# Daisy_Test.net
KiCad netlist of a schematic drawn in EAGLE
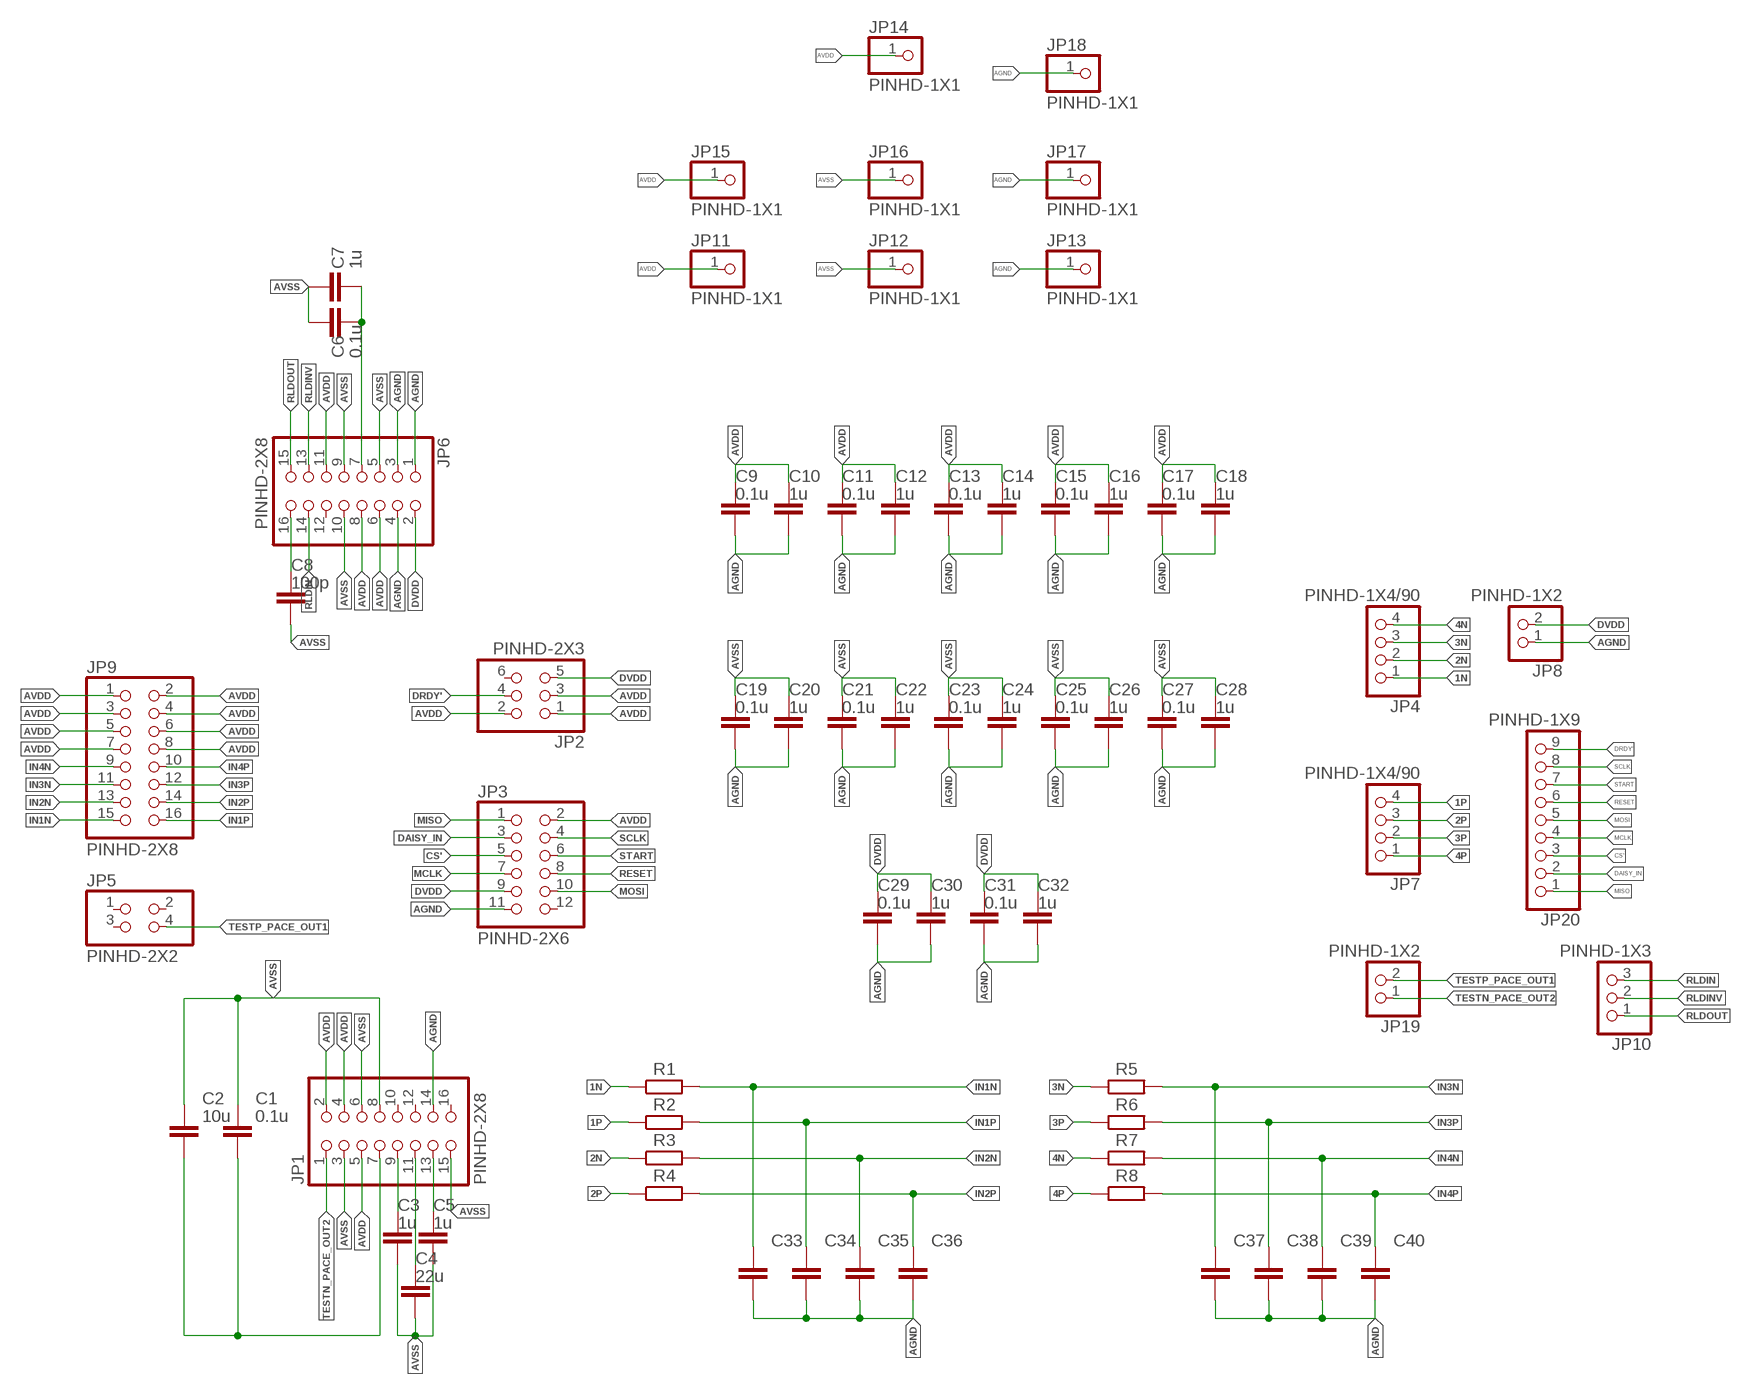
[diagram p0: schematic, sheet 1]

(export (version "E")
  (design (tool "Eeschema 10.0.6"))
  (components
    (comp (ref "C1")
      (value "0.1u")
      (footprint "eagle-import:CAPC2012X110")
      (libsource (lib "eagle-import") (part "CCHIP-0805(2012-METRIC)_"))
    )
    (comp (ref "C2")
      (value "10u")
      (footprint "eagle-import:CAPC2012X110")
      (libsource (lib "eagle-import") (part "CCHIP-0805(2012-METRIC)_"))
    )
    (comp (ref "C3")
      (value "1u")
      (footprint "eagle-import:CAPC2012X110")
      (libsource (lib "eagle-import") (part "CCHIP-0805(2012-METRIC)_"))
    )
    (comp (ref "C4")
      (value "22u")
      (footprint "eagle-import:CAPC2012X110")
      (libsource (lib "eagle-import") (part "CCHIP-0805(2012-METRIC)_"))
    )
    (comp (ref "C5")
      (value "1u")
      (footprint "eagle-import:CAPC2012X110")
      (libsource (lib "eagle-import") (part "CCHIP-0805(2012-METRIC)_"))
    )
    (comp (ref "C6")
      (value "0.1u")
      (footprint "eagle-import:CAPC2012X110")
      (libsource (lib "eagle-import") (part "CCHIP-0805(2012-METRIC)_"))
    )
    (comp (ref "C7")
      (value "1u")
      (footprint "eagle-import:CAPC2012X110")
      (libsource (lib "eagle-import") (part "CCHIP-0805(2012-METRIC)_"))
    )
    (comp (ref "C8")
      (value "100p")
      (footprint "eagle-import:CAPC2012X110")
      (libsource (lib "eagle-import") (part "CCHIP-0805(2012-METRIC)_"))
    )
    (comp (ref "C9")
      (value "0.1u")
      (footprint "eagle-import:CAPC2012X110")
      (libsource (lib "eagle-import") (part "CCHIP-0805(2012-METRIC)_"))
    )
    (comp (ref "C10")
      (value "1u")
      (footprint "eagle-import:CAPC2012X110")
      (libsource (lib "eagle-import") (part "CCHIP-0805(2012-METRIC)_"))
    )
    (comp (ref "C11")
      (value "0.1u")
      (footprint "eagle-import:CAPC2012X110")
      (libsource (lib "eagle-import") (part "CCHIP-0805(2012-METRIC)_"))
    )
    (comp (ref "C12")
      (value "1u")
      (footprint "eagle-import:CAPC2012X110")
      (libsource (lib "eagle-import") (part "CCHIP-0805(2012-METRIC)_"))
    )
    (comp (ref "C13")
      (value "0.1u")
      (footprint "eagle-import:CAPC2012X110")
      (libsource (lib "eagle-import") (part "CCHIP-0805(2012-METRIC)_"))
    )
    (comp (ref "C14")
      (value "1u")
      (footprint "eagle-import:CAPC2012X110")
      (libsource (lib "eagle-import") (part "CCHIP-0805(2012-METRIC)_"))
    )
    (comp (ref "C15")
      (value "0.1u")
      (footprint "eagle-import:CAPC2012X110")
      (libsource (lib "eagle-import") (part "CCHIP-0805(2012-METRIC)_"))
    )
    (comp (ref "C16")
      (value "1u")
      (footprint "eagle-import:CAPC2012X110")
      (libsource (lib "eagle-import") (part "CCHIP-0805(2012-METRIC)_"))
    )
    (comp (ref "C17")
      (value "0.1u")
      (footprint "eagle-import:CAPC2012X110")
      (libsource (lib "eagle-import") (part "CCHIP-0805(2012-METRIC)_"))
    )
    (comp (ref "C18")
      (value "1u")
      (footprint "eagle-import:CAPC2012X110")
      (libsource (lib "eagle-import") (part "CCHIP-0805(2012-METRIC)_"))
    )
    (comp (ref "C19")
      (value "0.1u")
      (footprint "eagle-import:CAPC2012X110")
      (libsource (lib "eagle-import") (part "CCHIP-0805(2012-METRIC)_"))
    )
    (comp (ref "C20")
      (value "1u")
      (footprint "eagle-import:CAPC2012X110")
      (libsource (lib "eagle-import") (part "CCHIP-0805(2012-METRIC)_"))
    )
    (comp (ref "C21")
      (value "0.1u")
      (footprint "eagle-import:CAPC2012X110")
      (libsource (lib "eagle-import") (part "CCHIP-0805(2012-METRIC)_"))
    )
    (comp (ref "C22")
      (value "1u")
      (footprint "eagle-import:CAPC2012X110")
      (libsource (lib "eagle-import") (part "CCHIP-0805(2012-METRIC)_"))
    )
    (comp (ref "C23")
      (value "0.1u")
      (footprint "eagle-import:CAPC2012X110")
      (libsource (lib "eagle-import") (part "CCHIP-0805(2012-METRIC)_"))
    )
    (comp (ref "C24")
      (value "1u")
      (footprint "eagle-import:CAPC2012X110")
      (libsource (lib "eagle-import") (part "CCHIP-0805(2012-METRIC)_"))
    )
    (comp (ref "C25")
      (value "0.1u")
      (footprint "eagle-import:CAPC2012X110")
      (libsource (lib "eagle-import") (part "CCHIP-0805(2012-METRIC)_"))
    )
    (comp (ref "C26")
      (value "1u")
      (footprint "eagle-import:CAPC2012X110")
      (libsource (lib "eagle-import") (part "CCHIP-0805(2012-METRIC)_"))
    )
    (comp (ref "C27")
      (value "0.1u")
      (footprint "eagle-import:CAPC2012X110")
      (libsource (lib "eagle-import") (part "CCHIP-0805(2012-METRIC)_"))
    )
    (comp (ref "C28")
      (value "1u")
      (footprint "eagle-import:CAPC2012X110")
      (libsource (lib "eagle-import") (part "CCHIP-0805(2012-METRIC)_"))
    )
    (comp (ref "C29")
      (value "0.1u")
      (footprint "eagle-import:CAPC2012X110")
      (libsource (lib "eagle-import") (part "CCHIP-0805(2012-METRIC)_"))
    )
    (comp (ref "C30")
      (value "1u")
      (footprint "eagle-import:CAPC2012X110")
      (libsource (lib "eagle-import") (part "CCHIP-0805(2012-METRIC)_"))
    )
    (comp (ref "C31")
      (value "0.1u")
      (footprint "eagle-import:CAPC2012X110")
      (libsource (lib "eagle-import") (part "CCHIP-0805(2012-METRIC)_"))
    )
    (comp (ref "C32")
      (value "1u")
      (footprint "eagle-import:CAPC2012X110")
      (libsource (lib "eagle-import") (part "CCHIP-0805(2012-METRIC)_"))
    )
    (comp (ref "C33")
      (value "C_CHIP-0805(2012-METRIC)")
      (footprint "eagle-import:CAPC2012X110")
      (libsource (lib "eagle-import") (part "CCHIP-0805(2012-METRIC)_"))
    )
    (comp (ref "C34")
      (value "C_CHIP-0805(2012-METRIC)")
      (footprint "eagle-import:CAPC2012X110")
      (libsource (lib "eagle-import") (part "CCHIP-0805(2012-METRIC)_"))
    )
    (comp (ref "C35")
      (value "C_CHIP-0805(2012-METRIC)")
      (footprint "eagle-import:CAPC2012X110")
      (libsource (lib "eagle-import") (part "CCHIP-0805(2012-METRIC)_"))
    )
    (comp (ref "C36")
      (value "C_CHIP-0805(2012-METRIC)")
      (footprint "eagle-import:CAPC2012X110")
      (libsource (lib "eagle-import") (part "CCHIP-0805(2012-METRIC)_"))
    )
    (comp (ref "C37")
      (value "C_CHIP-0805(2012-METRIC)")
      (footprint "eagle-import:CAPC2012X110")
      (libsource (lib "eagle-import") (part "CCHIP-0805(2012-METRIC)_"))
    )
    (comp (ref "C38")
      (value "C_CHIP-0805(2012-METRIC)")
      (footprint "eagle-import:CAPC2012X110")
      (libsource (lib "eagle-import") (part "CCHIP-0805(2012-METRIC)_"))
    )
    (comp (ref "C39")
      (value "C_CHIP-0805(2012-METRIC)")
      (footprint "eagle-import:CAPC2012X110")
      (libsource (lib "eagle-import") (part "CCHIP-0805(2012-METRIC)_"))
    )
    (comp (ref "C40")
      (value "C_CHIP-0805(2012-METRIC)")
      (footprint "eagle-import:CAPC2012X110")
      (libsource (lib "eagle-import") (part "CCHIP-0805(2012-METRIC)_"))
    )
    (comp (ref "JP1")
      (value "PINHD-2X8")
      (footprint "eagle-import:2X08")
      (libsource (lib "eagle-import") (part "PINHD-2X8"))
    )
    (comp (ref "JP2")
      (value "PINHD-2X3")
      (footprint "eagle-import:2X03")
      (libsource (lib "eagle-import") (part "PINHD-2X3"))
    )
    (comp (ref "JP3")
      (value "PINHD-2X6")
      (footprint "eagle-import:2X06")
      (libsource (lib "eagle-import") (part "PINHD-2X6"))
    )
    (comp (ref "JP4")
      (value "PINHD-1X4/90")
      (footprint "eagle-import:1X04_90")
      (libsource (lib "eagle-import") (part "PINHD-1X4/90"))
    )
    (comp (ref "JP5")
      (value "PINHD-2X2")
      (footprint "eagle-import:2X02")
      (libsource (lib "eagle-import") (part "PINHD-2X2"))
    )
    (comp (ref "JP6")
      (value "PINHD-2X8")
      (footprint "eagle-import:2X08")
      (libsource (lib "eagle-import") (part "PINHD-2X8"))
    )
    (comp (ref "JP7")
      (value "PINHD-1X4/90")
      (footprint "eagle-import:1X04_90")
      (libsource (lib "eagle-import") (part "PINHD-1X4/90"))
    )
    (comp (ref "JP8")
      (value "PINHD-1X2")
      (footprint "eagle-import:1X02")
      (libsource (lib "eagle-import") (part "PINHD-1X2"))
    )
    (comp (ref "JP9")
      (value "PINHD-2X8")
      (footprint "eagle-import:2X08")
      (libsource (lib "eagle-import") (part "PINHD-2X8"))
    )
    (comp (ref "JP10")
      (value "PINHD-1X3")
      (footprint "eagle-import:1X03")
      (libsource (lib "eagle-import") (part "PINHD-1X3"))
    )
    (comp (ref "JP11")
      (value "PINHD-1X1")
      (footprint "eagle-import:1X01")
      (libsource (lib "eagle-import") (part "PINHD-1X1"))
    )
    (comp (ref "JP12")
      (value "PINHD-1X1")
      (footprint "eagle-import:1X01")
      (libsource (lib "eagle-import") (part "PINHD-1X1"))
    )
    (comp (ref "JP13")
      (value "PINHD-1X1")
      (footprint "eagle-import:1X01")
      (libsource (lib "eagle-import") (part "PINHD-1X1"))
    )
    (comp (ref "JP14")
      (value "PINHD-1X1")
      (footprint "eagle-import:1X01")
      (libsource (lib "eagle-import") (part "PINHD-1X1"))
    )
    (comp (ref "JP15")
      (value "PINHD-1X1")
      (footprint "eagle-import:1X01")
      (libsource (lib "eagle-import") (part "PINHD-1X1"))
    )
    (comp (ref "JP16")
      (value "PINHD-1X1")
      (footprint "eagle-import:1X01")
      (libsource (lib "eagle-import") (part "PINHD-1X1"))
    )
    (comp (ref "JP17")
      (value "PINHD-1X1")
      (footprint "eagle-import:1X01")
      (libsource (lib "eagle-import") (part "PINHD-1X1"))
    )
    (comp (ref "JP18")
      (value "PINHD-1X1")
      (footprint "eagle-import:1X01")
      (libsource (lib "eagle-import") (part "PINHD-1X1"))
    )
    (comp (ref "JP19")
      (value "PINHD-1X2")
      (footprint "eagle-import:1X02")
      (libsource (lib "eagle-import") (part "PINHD-1X2"))
    )
    (comp (ref "JP20")
      (value "PINHD-1X9")
      (footprint "eagle-import:1X09")
      (libsource (lib "eagle-import") (part "PINHD-1X9"))
    )
    (comp (ref "R1")
      (value "R_CHIP-1206(3216-METRIC)")
      (footprint "eagle-import:RESC3216X70")
      (libsource (lib "eagle-import") (part "RCHIP-1206(3216-METRIC)_"))
    )
    (comp (ref "R2")
      (value "R_CHIP-1206(3216-METRIC)")
      (footprint "eagle-import:RESC3216X70")
      (libsource (lib "eagle-import") (part "RCHIP-1206(3216-METRIC)_"))
    )
    (comp (ref "R3")
      (value "R_CHIP-1206(3216-METRIC)")
      (footprint "eagle-import:RESC3216X70")
      (libsource (lib "eagle-import") (part "RCHIP-1206(3216-METRIC)_"))
    )
    (comp (ref "R4")
      (value "R_CHIP-1206(3216-METRIC)")
      (footprint "eagle-import:RESC3216X70")
      (libsource (lib "eagle-import") (part "RCHIP-1206(3216-METRIC)_"))
    )
    (comp (ref "R5")
      (value "R_CHIP-1206(3216-METRIC)")
      (footprint "eagle-import:RESC3216X70")
      (libsource (lib "eagle-import") (part "RCHIP-1206(3216-METRIC)_"))
    )
    (comp (ref "R6")
      (value "R_CHIP-1206(3216-METRIC)")
      (footprint "eagle-import:RESC3216X70")
      (libsource (lib "eagle-import") (part "RCHIP-1206(3216-METRIC)_"))
    )
    (comp (ref "R7")
      (value "R_CHIP-1206(3216-METRIC)")
      (footprint "eagle-import:RESC3216X70")
      (libsource (lib "eagle-import") (part "RCHIP-1206(3216-METRIC)_"))
    )
    (comp (ref "R8")
      (value "R_CHIP-1206(3216-METRIC)")
      (footprint "eagle-import:RESC3216X70")
      (libsource (lib "eagle-import") (part "RCHIP-1206(3216-METRIC)_"))
    )
  )
  (nets
    (net (code "1") (name "1N") (class "Default")
      (node (ref "JP4") (pin "1") (pinfunction "1_1") (pintype "passive"))
      (node (ref "R1") (pin "1") (pinfunction "1_1") (pintype "passive"))
    )
    (net (code "2") (name "1P") (class "Default")
      (node (ref "JP7") (pin "4") (pinfunction "4_4") (pintype "passive"))
      (node (ref "R2") (pin "1") (pinfunction "1_1") (pintype "passive"))
    )
    (net (code "3") (name "2N") (class "Default")
      (node (ref "JP4") (pin "2") (pinfunction "2_2") (pintype "passive"))
      (node (ref "R3") (pin "1") (pinfunction "1_1") (pintype "passive"))
    )
    (net (code "4") (name "2P") (class "Default")
      (node (ref "JP7") (pin "3") (pinfunction "3_3") (pintype "passive"))
      (node (ref "R4") (pin "1") (pinfunction "1_1") (pintype "passive"))
    )
    (net (code "5") (name "3N") (class "Default")
      (node (ref "JP4") (pin "3") (pinfunction "3_3") (pintype "passive"))
      (node (ref "R5") (pin "1") (pinfunction "1_1") (pintype "passive"))
    )
    (net (code "6") (name "3P") (class "Default")
      (node (ref "JP7") (pin "2") (pinfunction "2_2") (pintype "passive"))
      (node (ref "R6") (pin "1") (pinfunction "1_1") (pintype "passive"))
    )
    (net (code "7") (name "4N") (class "Default")
      (node (ref "JP4") (pin "4") (pinfunction "4_4") (pintype "passive"))
      (node (ref "R7") (pin "1") (pinfunction "1_1") (pintype "passive"))
    )
    (net (code "8") (name "4P") (class "Default")
      (node (ref "JP7") (pin "1") (pinfunction "1_1") (pintype "passive"))
      (node (ref "R8") (pin "1") (pinfunction "1_1") (pintype "passive"))
    )
    (net (code "9") (name "AGND") (class "Default")
      (node (ref "C10") (pin "2") (pinfunction "2_2") (pintype "passive"))
      (node (ref "C11") (pin "2") (pinfunction "2_2") (pintype "passive"))
      (node (ref "C12") (pin "2") (pinfunction "2_2") (pintype "passive"))
      (node (ref "C13") (pin "2") (pinfunction "2_2") (pintype "passive"))
      (node (ref "C14") (pin "2") (pinfunction "2_2") (pintype "passive"))
      (node (ref "C15") (pin "2") (pinfunction "2_2") (pintype "passive"))
      (node (ref "C16") (pin "2") (pinfunction "2_2") (pintype "passive"))
      (node (ref "C17") (pin "2") (pinfunction "2_2") (pintype "passive"))
      (node (ref "C18") (pin "2") (pinfunction "2_2") (pintype "passive"))
      (node (ref "C19") (pin "2") (pinfunction "2_2") (pintype "passive"))
      (node (ref "C20") (pin "2") (pinfunction "2_2") (pintype "passive"))
      (node (ref "C21") (pin "2") (pinfunction "2_2") (pintype "passive"))
      (node (ref "C22") (pin "2") (pinfunction "2_2") (pintype "passive"))
      (node (ref "C23") (pin "2") (pinfunction "2_2") (pintype "passive"))
      (node (ref "C24") (pin "2") (pinfunction "2_2") (pintype "passive"))
      (node (ref "C25") (pin "2") (pinfunction "2_2") (pintype "passive"))
      (node (ref "C26") (pin "2") (pinfunction "2_2") (pintype "passive"))
      (node (ref "C27") (pin "2") (pinfunction "2_2") (pintype "passive"))
      (node (ref "C28") (pin "2") (pinfunction "2_2") (pintype "passive"))
      (node (ref "C29") (pin "2") (pinfunction "2_2") (pintype "passive"))
      (node (ref "C30") (pin "2") (pinfunction "2_2") (pintype "passive"))
      (node (ref "C31") (pin "2") (pinfunction "2_2") (pintype "passive"))
      (node (ref "C32") (pin "2") (pinfunction "2_2") (pintype "passive"))
      (node (ref "C33") (pin "2") (pinfunction "2_2") (pintype "passive"))
      (node (ref "C34") (pin "2") (pinfunction "2_2") (pintype "passive"))
      (node (ref "C35") (pin "2") (pinfunction "2_2") (pintype "passive"))
      (node (ref "C36") (pin "2") (pinfunction "2_2") (pintype "passive"))
      (node (ref "C37") (pin "2") (pinfunction "2_2") (pintype "passive"))
      (node (ref "C38") (pin "2") (pinfunction "2_2") (pintype "passive"))
      (node (ref "C39") (pin "2") (pinfunction "2_2") (pintype "passive"))
      (node (ref "C40") (pin "2") (pinfunction "2_2") (pintype "passive"))
      (node (ref "C9") (pin "2") (pinfunction "2_2") (pintype "passive"))
      (node (ref "JP1") (pin "14") (pinfunction "14_14") (pintype "passive"))
      (node (ref "JP13") (pin "1") (pinfunction "1_1") (pintype "passive"))
      (node (ref "JP17") (pin "1") (pinfunction "1_1") (pintype "passive"))
      (node (ref "JP18") (pin "1") (pinfunction "1_1") (pintype "passive"))
      (node (ref "JP3") (pin "11") (pinfunction "11_11") (pintype "passive"))
      (node (ref "JP6") (pin "1") (pinfunction "1_1") (pintype "passive"))
      (node (ref "JP6") (pin "3") (pinfunction "3_3") (pintype "passive"))
      (node (ref "JP6") (pin "4") (pinfunction "4_4") (pintype "passive"))
      (node (ref "JP8") (pin "1") (pinfunction "1_1") (pintype "passive"))
    )
    (net (code "10") (name "AVDD") (class "Default")
      (node (ref "C10") (pin "1") (pinfunction "1_1") (pintype "passive"))
      (node (ref "C11") (pin "1") (pinfunction "1_1") (pintype "passive"))
      (node (ref "C12") (pin "1") (pinfunction "1_1") (pintype "passive"))
      (node (ref "C13") (pin "1") (pinfunction "1_1") (pintype "passive"))
      (node (ref "C14") (pin "1") (pinfunction "1_1") (pintype "passive"))
      (node (ref "C15") (pin "1") (pinfunction "1_1") (pintype "passive"))
      (node (ref "C16") (pin "1") (pinfunction "1_1") (pintype "passive"))
      (node (ref "C17") (pin "1") (pinfunction "1_1") (pintype "passive"))
      (node (ref "C18") (pin "1") (pinfunction "1_1") (pintype "passive"))
      (node (ref "C9") (pin "1") (pinfunction "1_1") (pintype "passive"))
      (node (ref "JP1") (pin "2") (pinfunction "2_2") (pintype "passive"))
      (node (ref "JP1") (pin "4") (pinfunction "4_4") (pintype "passive"))
      (node (ref "JP1") (pin "5") (pinfunction "5_5") (pintype "passive"))
      (node (ref "JP11") (pin "1") (pinfunction "1_1") (pintype "passive"))
      (node (ref "JP14") (pin "1") (pinfunction "1_1") (pintype "passive"))
      (node (ref "JP15") (pin "1") (pinfunction "1_1") (pintype "passive"))
      (node (ref "JP2") (pin "1") (pinfunction "1_1") (pintype "passive"))
      (node (ref "JP2") (pin "2") (pinfunction "2_2") (pintype "passive"))
      (node (ref "JP2") (pin "3") (pinfunction "3_3") (pintype "passive"))
      (node (ref "JP3") (pin "2") (pinfunction "2_2") (pintype "passive"))
      (node (ref "JP6") (pin "11") (pinfunction "11_11") (pintype "passive"))
      (node (ref "JP6") (pin "6") (pinfunction "6_6") (pintype "passive"))
      (node (ref "JP6") (pin "8") (pinfunction "8_8") (pintype "passive"))
      (node (ref "JP9") (pin "1") (pinfunction "1_1") (pintype "passive"))
      (node (ref "JP9") (pin "2") (pinfunction "2_2") (pintype "passive"))
      (node (ref "JP9") (pin "3") (pinfunction "3_3") (pintype "passive"))
      (node (ref "JP9") (pin "4") (pinfunction "4_4") (pintype "passive"))
      (node (ref "JP9") (pin "5") (pinfunction "5_5") (pintype "passive"))
      (node (ref "JP9") (pin "6") (pinfunction "6_6") (pintype "passive"))
      (node (ref "JP9") (pin "7") (pinfunction "7_7") (pintype "passive"))
      (node (ref "JP9") (pin "8") (pinfunction "8_8") (pintype "passive"))
    )
    (net (code "11") (name "AVSS") (class "Default")
      (node (ref "C1") (pin "1") (pinfunction "1_1") (pintype "passive"))
      (node (ref "C19") (pin "1") (pinfunction "1_1") (pintype "passive"))
      (node (ref "C2") (pin "1") (pinfunction "1_1") (pintype "passive"))
      (node (ref "C20") (pin "1") (pinfunction "1_1") (pintype "passive"))
      (node (ref "C21") (pin "1") (pinfunction "1_1") (pintype "passive"))
      (node (ref "C22") (pin "1") (pinfunction "1_1") (pintype "passive"))
      (node (ref "C23") (pin "1") (pinfunction "1_1") (pintype "passive"))
      (node (ref "C24") (pin "1") (pinfunction "1_1") (pintype "passive"))
      (node (ref "C25") (pin "1") (pinfunction "1_1") (pintype "passive"))
      (node (ref "C26") (pin "1") (pinfunction "1_1") (pintype "passive"))
      (node (ref "C27") (pin "1") (pinfunction "1_1") (pintype "passive"))
      (node (ref "C28") (pin "1") (pinfunction "1_1") (pintype "passive"))
      (node (ref "C3") (pin "2") (pinfunction "2_2") (pintype "passive"))
      (node (ref "C4") (pin "2") (pinfunction "2_2") (pintype "passive"))
      (node (ref "C5") (pin "2") (pinfunction "2_2") (pintype "passive"))
      (node (ref "C6") (pin "1") (pinfunction "1_1") (pintype "passive"))
      (node (ref "C7") (pin "1") (pinfunction "1_1") (pintype "passive"))
      (node (ref "C8") (pin "2") (pinfunction "2_2") (pintype "passive"))
      (node (ref "JP1") (pin "15") (pinfunction "15_15") (pintype "passive"))
      (node (ref "JP1") (pin "3") (pinfunction "3_3") (pintype "passive"))
      (node (ref "JP1") (pin "6") (pinfunction "6_6") (pintype "passive"))
      (node (ref "JP1") (pin "8") (pinfunction "8_8") (pintype "passive"))
      (node (ref "JP12") (pin "1") (pinfunction "1_1") (pintype "passive"))
      (node (ref "JP16") (pin "1") (pinfunction "1_1") (pintype "passive"))
      (node (ref "JP6") (pin "10") (pinfunction "10_10") (pintype "passive"))
      (node (ref "JP6") (pin "5") (pinfunction "5_5") (pintype "passive"))
      (node (ref "JP6") (pin "9") (pinfunction "9_9") (pintype "passive"))
    )
    (net (code "12") (name "CS'") (class "Default")
      (node (ref "JP20") (pin "3") (pinfunction "3_3") (pintype "passive"))
      (node (ref "JP3") (pin "5") (pinfunction "5_5") (pintype "passive"))
    )
    (net (code "13") (name "DAISY_IN") (class "Default")
      (node (ref "JP20") (pin "2") (pinfunction "2_2") (pintype "passive"))
      (node (ref "JP3") (pin "3") (pinfunction "3_3") (pintype "passive"))
    )
    (net (code "14") (name "DRDY'") (class "Default")
      (node (ref "JP2") (pin "4") (pinfunction "4_4") (pintype "passive"))
      (node (ref "JP20") (pin "9") (pinfunction "9_9") (pintype "passive"))
    )
    (net (code "15") (name "DVDD") (class "Default")
      (node (ref "C29") (pin "1") (pinfunction "1_1") (pintype "passive"))
      (node (ref "C30") (pin "1") (pinfunction "1_1") (pintype "passive"))
      (node (ref "C31") (pin "1") (pinfunction "1_1") (pintype "passive"))
      (node (ref "C32") (pin "1") (pinfunction "1_1") (pintype "passive"))
      (node (ref "JP2") (pin "5") (pinfunction "5_5") (pintype "passive"))
      (node (ref "JP3") (pin "9") (pinfunction "9_9") (pintype "passive"))
      (node (ref "JP6") (pin "2") (pinfunction "2_2") (pintype "passive"))
      (node (ref "JP8") (pin "2") (pinfunction "2_2") (pintype "passive"))
    )
    (net (code "16") (name "IN1N") (class "Default")
      (node (ref "C33") (pin "1") (pinfunction "1_1") (pintype "passive"))
      (node (ref "JP9") (pin "15") (pinfunction "15_15") (pintype "passive"))
      (node (ref "R1") (pin "2") (pinfunction "2_2") (pintype "passive"))
    )
    (net (code "17") (name "IN1P") (class "Default")
      (node (ref "C34") (pin "1") (pinfunction "1_1") (pintype "passive"))
      (node (ref "JP9") (pin "16") (pinfunction "16_16") (pintype "passive"))
      (node (ref "R2") (pin "2") (pinfunction "2_2") (pintype "passive"))
    )
    (net (code "18") (name "IN2N") (class "Default")
      (node (ref "C35") (pin "1") (pinfunction "1_1") (pintype "passive"))
      (node (ref "JP9") (pin "13") (pinfunction "13_13") (pintype "passive"))
      (node (ref "R3") (pin "2") (pinfunction "2_2") (pintype "passive"))
    )
    (net (code "19") (name "IN2P") (class "Default")
      (node (ref "C36") (pin "1") (pinfunction "1_1") (pintype "passive"))
      (node (ref "JP9") (pin "14") (pinfunction "14_14") (pintype "passive"))
      (node (ref "R4") (pin "2") (pinfunction "2_2") (pintype "passive"))
    )
    (net (code "20") (name "IN3N") (class "Default")
      (node (ref "C37") (pin "1") (pinfunction "1_1") (pintype "passive"))
      (node (ref "JP9") (pin "11") (pinfunction "11_11") (pintype "passive"))
      (node (ref "R5") (pin "2") (pinfunction "2_2") (pintype "passive"))
    )
    (net (code "21") (name "IN3P") (class "Default")
      (node (ref "C38") (pin "1") (pinfunction "1_1") (pintype "passive"))
      (node (ref "JP9") (pin "12") (pinfunction "12_12") (pintype "passive"))
      (node (ref "R6") (pin "2") (pinfunction "2_2") (pintype "passive"))
    )
    (net (code "22") (name "IN4N") (class "Default")
      (node (ref "C39") (pin "1") (pinfunction "1_1") (pintype "passive"))
      (node (ref "JP9") (pin "9") (pinfunction "9_9") (pintype "passive"))
      (node (ref "R7") (pin "2") (pinfunction "2_2") (pintype "passive"))
    )
    (net (code "23") (name "IN4P") (class "Default")
      (node (ref "C40") (pin "1") (pinfunction "1_1") (pintype "passive"))
      (node (ref "JP9") (pin "10") (pinfunction "10_10") (pintype "passive"))
      (node (ref "R8") (pin "2") (pinfunction "2_2") (pintype "passive"))
    )
    (net (code "24") (name "MCLK") (class "Default")
      (node (ref "JP20") (pin "4") (pinfunction "4_4") (pintype "passive"))
      (node (ref "JP3") (pin "7") (pinfunction "7_7") (pintype "passive"))
    )
    (net (code "25") (name "MISO") (class "Default")
      (node (ref "JP20") (pin "1") (pinfunction "1_1") (pintype "passive"))
      (node (ref "JP3") (pin "1") (pinfunction "1_1") (pintype "passive"))
    )
    (net (code "26") (name "MOSI") (class "Default")
      (node (ref "JP20") (pin "5") (pinfunction "5_5") (pintype "passive"))
      (node (ref "JP3") (pin "10") (pinfunction "10_10") (pintype "passive"))
    )
    (net (code "27") (name "Net-(C1-Pad2)") (class "Default")
      (node (ref "C1") (pin "2") (pinfunction "2_2") (pintype "passive"))
      (node (ref "C2") (pin "2") (pinfunction "2_2") (pintype "passive"))
      (node (ref "JP1") (pin "7") (pinfunction "7_7") (pintype "passive"))
    )
    (net (code "28") (name "Net-(C3-Pad1)") (class "Default")
      (node (ref "C3") (pin "1") (pinfunction "1_1") (pintype "passive"))
      (node (ref "JP1") (pin "9") (pinfunction "9_9") (pintype "passive"))
    )
    (net (code "29") (name "Net-(C4-Pad1)") (class "Default")
      (node (ref "C4") (pin "1") (pinfunction "1_1") (pintype "passive"))
      (node (ref "JP1") (pin "11") (pinfunction "11_11") (pintype "passive"))
    )
    (net (code "30") (name "Net-(C5-Pad1)") (class "Default")
      (node (ref "C5") (pin "1") (pinfunction "1_1") (pintype "passive"))
      (node (ref "JP1") (pin "13") (pinfunction "13_13") (pintype "passive"))
    )
    (net (code "31") (name "Net-(C6-Pad2)") (class "Default")
      (node (ref "C6") (pin "2") (pinfunction "2_2") (pintype "passive"))
      (node (ref "C7") (pin "2") (pinfunction "2_2") (pintype "passive"))
      (node (ref "JP6") (pin "7") (pinfunction "7_7") (pintype "passive"))
    )
    (net (code "32") (name "Net-(C8-Pad1)") (class "Default")
      (node (ref "C8") (pin "1") (pinfunction "1_1") (pintype "passive"))
      (node (ref "JP6") (pin "16") (pinfunction "16_16") (pintype "passive"))
    )
    (net (code "33") (name "RESET") (class "Default")
      (node (ref "JP20") (pin "6") (pinfunction "6_6") (pintype "passive"))
      (node (ref "JP3") (pin "8") (pinfunction "8_8") (pintype "passive"))
    )
    (net (code "34") (name "RLDIN") (class "Default")
      (node (ref "JP10") (pin "3") (pinfunction "3_3") (pintype "passive"))
      (node (ref "JP6") (pin "14") (pinfunction "14_14") (pintype "passive"))
    )
    (net (code "35") (name "RLDINV") (class "Default")
      (node (ref "JP10") (pin "2") (pinfunction "2_2") (pintype "passive"))
      (node (ref "JP6") (pin "13") (pinfunction "13_13") (pintype "passive"))
    )
    (net (code "36") (name "RLDOUT") (class "Default")
      (node (ref "JP10") (pin "1") (pinfunction "1_1") (pintype "passive"))
      (node (ref "JP6") (pin "15") (pinfunction "15_15") (pintype "passive"))
    )
    (net (code "37") (name "SCLK") (class "Default")
      (node (ref "JP20") (pin "8") (pinfunction "8_8") (pintype "passive"))
      (node (ref "JP3") (pin "4") (pinfunction "4_4") (pintype "passive"))
    )
    (net (code "38") (name "START") (class "Default")
      (node (ref "JP20") (pin "7") (pinfunction "7_7") (pintype "passive"))
      (node (ref "JP3") (pin "6") (pinfunction "6_6") (pintype "passive"))
    )
    (net (code "39") (name "TESTN_PACE_OUT2") (class "Default")
      (node (ref "JP1") (pin "1") (pinfunction "1_1") (pintype "passive"))
      (node (ref "JP19") (pin "1") (pinfunction "1_1") (pintype "passive"))
    )
    (net (code "40") (name "TESTP_PACE_OUT1") (class "Default")
      (node (ref "JP19") (pin "2") (pinfunction "2_2") (pintype "passive"))
      (node (ref "JP5") (pin "4") (pinfunction "4_4") (pintype "passive"))
    )
    (net (code "41") (name "unconnected-(JP1-Pad10)") (class "Default")
      (node (ref "JP1") (pin "10") (pinfunction "10_10") (pintype "passive"))
    )
    (net (code "42") (name "unconnected-(JP1-Pad12)") (class "Default")
      (node (ref "JP1") (pin "12") (pinfunction "12_12") (pintype "passive"))
    )
    (net (code "43") (name "unconnected-(JP1-Pad16)") (class "Default")
      (node (ref "JP1") (pin "16") (pinfunction "16_16") (pintype "passive"))
    )
    (net (code "44") (name "unconnected-(JP2-Pad6)") (class "Default")
      (node (ref "JP2") (pin "6") (pinfunction "6_6") (pintype "passive"))
    )
    (net (code "45") (name "unconnected-(JP3-Pad12)") (class "Default")
      (node (ref "JP3") (pin "12") (pinfunction "12_12") (pintype "passive"))
    )
    (net (code "46") (name "unconnected-(JP5-Pad1)") (class "Default")
      (node (ref "JP5") (pin "1") (pinfunction "1_1") (pintype "passive"))
    )
    (net (code "47") (name "unconnected-(JP5-Pad2)") (class "Default")
      (node (ref "JP5") (pin "2") (pinfunction "2_2") (pintype "passive"))
    )
    (net (code "48") (name "unconnected-(JP5-Pad3)") (class "Default")
      (node (ref "JP5") (pin "3") (pinfunction "3_3") (pintype "passive"))
    )
    (net (code "49") (name "unconnected-(JP6-Pad12)") (class "Default")
      (node (ref "JP6") (pin "12") (pinfunction "12_12") (pintype "passive"))
    )
  )
)
